# SMT_2inch_printer_060903.net
KiCad netlist of a schematic drawn in Altium Designer
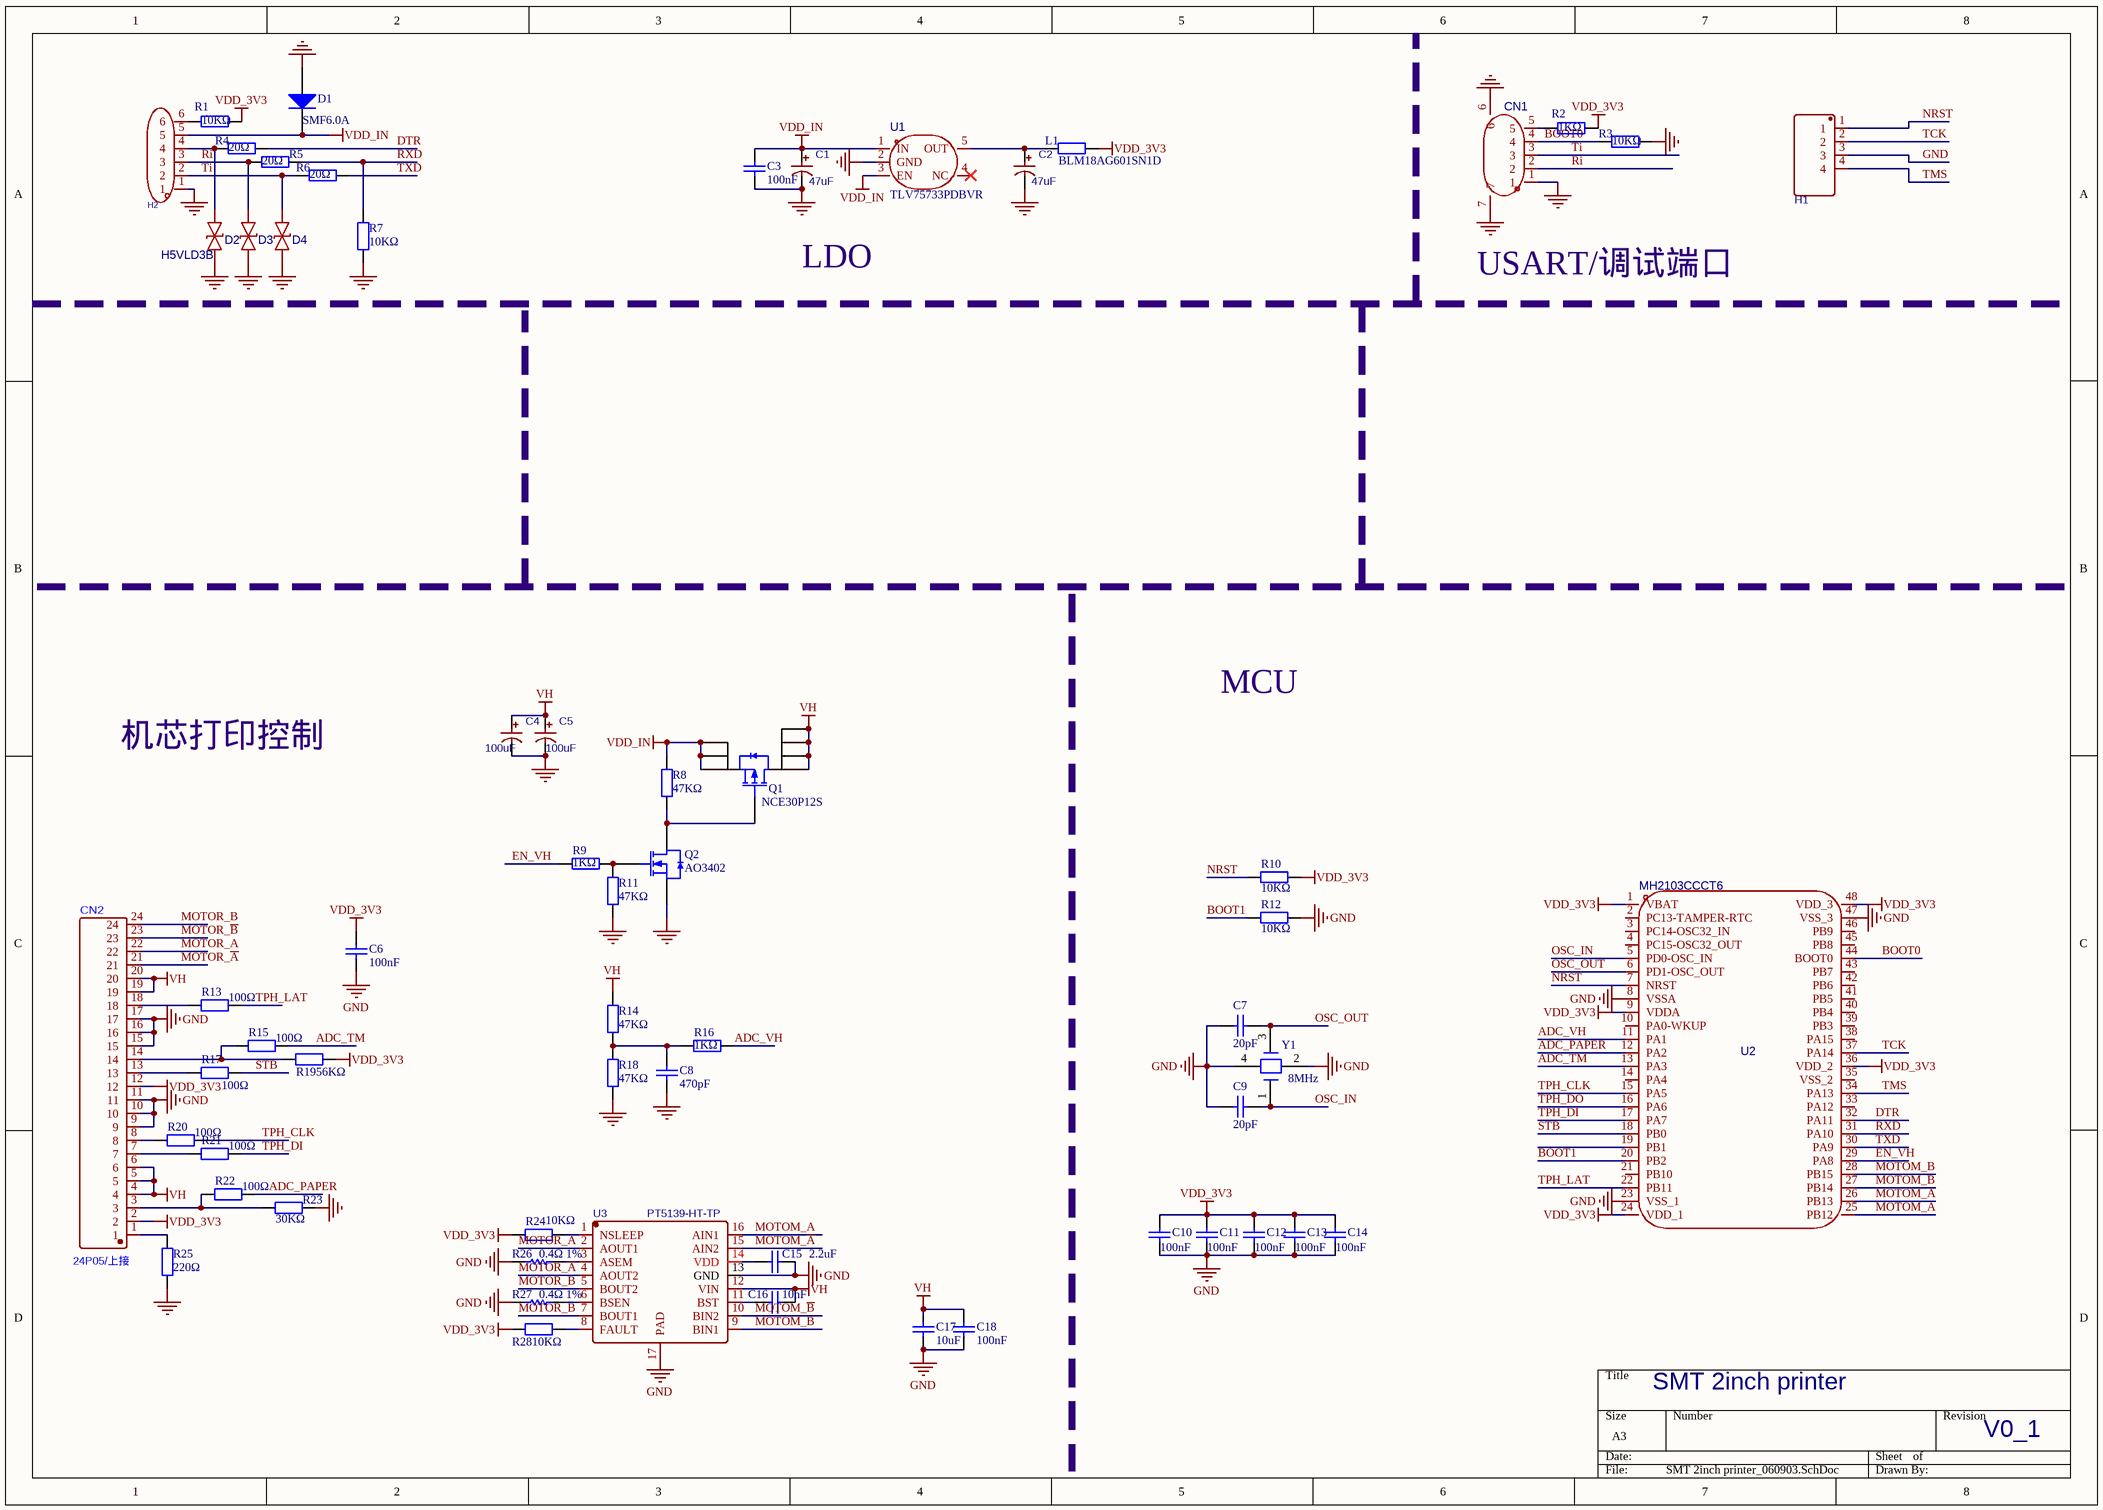
[diagram p0: SMT 2inch printer_060903.SchDoc]

(export (version "E")
  (design (tool "Eeschema 10.0.6"))
  (components
    (comp (ref "C1")
      (value "47uF")
      (footprint "CAP-SMD_BD6.3-L6.6-W6.6-FD")
      (fields
        (field (name "BOM_MANUFACTURER PART") "10uF 25V RHOS")
        (field (name "BOM_SUPPLIER PART") "C19576")
      )
      (libsource (lib "*") (part "10uF"))
    )
    (comp (ref "C2")
      (value "47uF")
      (footprint "CAP-SMD_BD6.3-L6.6-W6.6-FD")
      (fields
        (field (name "BOM_MANUFACTURER PART") "10uF 25V RHOS")
        (field (name "BOM_SUPPLIER PART") "C19576")
      )
      (libsource (lib "*") (part "10uF"))
    )
    (comp (ref "C3")
      (value "100nF")
      (footprint "0603_C")
      (description "贴片电容")
      (libsource (lib "*") (part "0603 100nF (104) 10% 50V"))
    )
    (comp (ref "C4")
      (value "100uF")
      (footprint "CAP-SMD_BD6.3-L6.6-W6.6-FD")
      (fields
        (field (name "BOM_MANUFACTURER PART") "10uF 25V RHOS")
        (field (name "BOM_SUPPLIER PART") "C19576")
      )
      (libsource (lib "*") (part "10uF"))
    )
    (comp (ref "C5")
      (value "100uF")
      (footprint "CAP-SMD_BD6.3-L6.6-W6.6-FD")
      (fields
        (field (name "BOM_MANUFACTURER PART") "10uF 25V RHOS")
        (field (name "BOM_SUPPLIER PART") "C19576")
      )
      (libsource (lib "*") (part "10uF"))
    )
    (comp (ref "C6")
      (value "100nF")
      (footprint "0603_C")
      (description "贴片电容")
      (libsource (lib "Miscellaneous Devices LC") (part "0603 100nF (104) 10% 50V"))
    )
    (comp (ref "C7")
      (value "20pF")
      (footprint "0603_C")
      (description "贴片电容")
      (libsource (lib "Miscellaneous Devices LC") (part "0603 10pF (100) 5% 50V"))
    )
    (comp (ref "C8")
      (value "470pF")
      (footprint "0603_C")
      (description "贴片电容")
      (libsource (lib "Miscellaneous Devices LC") (part "0603 100nF (104) 10% 50V"))
    )
    (comp (ref "C9")
      (value "20pF")
      (footprint "0603_C")
      (description "贴片电容")
      (libsource (lib "Miscellaneous Devices LC") (part "0603 10pF (100) 5% 50V"))
    )
    (comp (ref "C10")
      (value "100nF")
      (footprint "0603_C")
      (description "贴片电容")
      (libsource (lib "Miscellaneous Devices LC") (part "0603 100nF (104) 10% 50V"))
    )
    (comp (ref "C11")
      (value "100nF")
      (footprint "0603_C")
      (description "贴片电容")
      (libsource (lib "Miscellaneous Devices LC") (part "0603 100nF (104) 10% 50V"))
    )
    (comp (ref "C12")
      (value "100nF")
      (footprint "0603_C")
      (description "贴片电容")
      (libsource (lib "Miscellaneous Devices LC") (part "0603 100nF (104) 10% 50V"))
    )
    (comp (ref "C13")
      (value "100nF")
      (footprint "0603_C")
      (description "贴片电容")
      (libsource (lib "Miscellaneous Devices LC") (part "0603 100nF (104) 10% 50V"))
    )
    (comp (ref "C14")
      (value "100nF")
      (footprint "0603_C")
      (description "贴片电容")
      (libsource (lib "Miscellaneous Devices LC") (part "0603 100nF (104) 10% 50V"))
    )
    (comp (ref "C15")
      (value "2.2uF")
      (footprint "0603_C")
      (description "贴片电容")
      (libsource (lib "Miscellaneous Devices LC") (part "0805 2.2uF (225) 20% 50V"))
    )
    (comp (ref "C16")
      (value "10nF")
      (footprint "0603_C")
      (description "贴片电容")
      (libsource (lib "Miscellaneous Devices LC") (part "0603 10nF (103) 10% 50V"))
    )
    (comp (ref "C17")
      (value "10uF")
      (footprint "0603_C")
      (description "贴片电容")
      (libsource (lib "Miscellaneous Devices LC") (part "0805 10uF (106) 10% 25V"))
    )
    (comp (ref "C18")
      (value "100nF")
      (footprint "0603_C")
      (description "贴片电容")
      (libsource (lib "Miscellaneous Devices LC") (part "0603 100nF (104) 10% 50V"))
    )
    (comp (ref "CN1")
      (value "mx1.25mm-5p-wt")
      (footprint "CONN-SMD_5P-P1.25_MX1.25MM-5P-WT")
      (fields (field (name "MANUFACTURERPART") "MX1.25mm-5P-WT"))
      (libsource (lib "altium-import") (part "root_2_mx1.25mm-5p-wt_"))
    )
    (comp (ref "CN2")
      (value "24P05/上接")
      (footprint "FPC-SMD_24P-P0.50_F0500WR-S-24PNLNG1GB0R")
      (libsource (lib "altium-import") (part "root_2__"))
    )
    (comp (ref "D1")
      (value "SMF6.0A")
      (footprint "SOD-123FL_L2.7-W1.8-LS3.8-RD")
      (description "稳压二极管")
      (libsource (lib "*") (part "SOD-323 1N4148WS T4"))
    )
    (comp (ref "D2")
      (value "H5VLD3B")
      (footprint "SOD-323_L1.7-W1.3-LS2.5-BI")
      (libsource (lib "altium-import") (part "root_1_PESD5V0S1BA_C2827694_"))
    )
    (comp (ref "D3")
      (value "H5VLD3B")
      (footprint "SOD-323_L1.7-W1.3-LS2.5-BI")
      (libsource (lib "altium-import") (part "root_1_PESD5V0S1BA_C2827694_"))
    )
    (comp (ref "D4")
      (value "H5VLD3B")
      (footprint "SOD-323_L1.7-W1.3-LS2.5-BI")
      (libsource (lib "altium-import") (part "root_1_PESD5V0S1BA_C2827694_"))
    )
    (comp (ref "H1")
      (value "77311-462K05LF")
      (footprint "77311-462K05LF")
      (fields (field (name "BOM_SUPPLIER PART") "C180219") (field (name "CONTRIBUTOR") "LCSC"))
      (libsource (lib "*") (part "77311-462K05LF"))
    )
    (comp (ref "H2")
      (value "lail-pz2.54-6p-l")
      (footprint "HDR-TH_6P-P2.54-V-F")
      (fields (field (name "MANUFACTURERPART") "LAIL-PZ2.54-6P-L"))
      (libsource (lib "altium-import") (part "root_2_lail-pz2.54-6p-l_"))
    )
    (comp (ref "L1")
      (value "BLM18AG601SN1D")
      (footprint "0805_L")
      (description "贴片电阻")
      (libsource (lib "*") (part "0603 4.7KΩ (4701) 1%"))
    )
    (comp (ref "Q1")
      (value "NCE30P12S")
      (footprint "SOIC-8_150mil")
      (description "MOS(场效应管)")
      (libsource (lib "*") (part "AO4407A"))
    )
    (comp (ref "Q2")
      (value "AO3402")
      (footprint "SOT-23-3L")
      (description "MOS(场效应管)")
      (libsource (lib "*") (part "AO3402A N道沟 X0YV1T SOT-23"))
    )
    (comp (ref "R1")
      (value "10KΩ")
      (footprint "0603_R")
      (description "贴片电阻")
      (libsource (lib "*") (part "0603 4.7KΩ (4701) 1%"))
    )
    (comp (ref "R2")
      (value "1KΩ")
      (footprint "0603_R")
      (description "贴片电阻")
      (libsource (lib "*") (part "0603 4.7KΩ (4701) 1%"))
    )
    (comp (ref "R3")
      (value "10KΩ")
      (footprint "0603_R")
      (description "贴片电阻")
      (libsource (lib "*") (part "0603 4.7KΩ (4701) 1%"))
    )
    (comp (ref "R4")
      (value "20Ω")
      (footprint "0603_R")
      (description "贴片电阻")
      (libsource (lib "*") (part "0603 100Ω (1000) 1%"))
    )
    (comp (ref "R5")
      (value "20Ω")
      (footprint "0603_R")
      (description "贴片电阻")
      (libsource (lib "*") (part "0603 100Ω (1000) 1%"))
    )
    (comp (ref "R6")
      (value "20Ω")
      (footprint "0603_R")
      (description "贴片电阻")
      (libsource (lib "*") (part "0603 100Ω (1000) 1%"))
    )
    (comp (ref "R7")
      (value "10KΩ")
      (footprint "0603_R")
      (description "贴片电阻")
      (libsource (lib "") (part "0603 4.7KΩ (4701) 1%_2"))
    )
    (comp (ref "R8")
      (value "47KΩ")
      (footprint "0603_R")
      (description "贴片电阻")
      (libsource (lib "*") (part "0603 47KΩ (4702) 1%"))
    )
    (comp (ref "R9")
      (value "1KΩ")
      (footprint "0603_R")
      (description "贴片电阻")
      (libsource (lib "*") (part "0603 470Ω (4700) 1%"))
    )
    (comp (ref "R10")
      (value "10KΩ")
      (footprint "0603_R")
      (description "贴片电阻")
      (libsource (lib "Miscellaneous Devices LC") (part "0603 4.7KΩ (4701) 1%"))
    )
    (comp (ref "R11")
      (value "47KΩ")
      (footprint "0603_R")
      (description "贴片电阻")
      (libsource (lib "") (part "0603 4.7KΩ (4701) 1%_1"))
    )
    (comp (ref "R12")
      (value "10KΩ")
      (footprint "0603_R")
      (description "贴片电阻")
      (libsource (lib "Miscellaneous Devices LC") (part "0603 4.7KΩ (4701) 1%"))
    )
    (comp (ref "R13")
      (value "100Ω")
      (footprint "0603_R")
      (description "贴片电阻")
      (libsource (lib "Miscellaneous Devices LC") (part "0603 10KΩ (1002) 1%"))
    )
    (comp (ref "R14")
      (value "47KΩ")
      (footprint "0603_R")
      (description "贴片电阻")
      (libsource (lib "") (part "0603 4.7KΩ (4701) 1%_1"))
    )
    (comp (ref "R15")
      (value "100Ω")
      (footprint "0603_R")
      (description "贴片电阻")
      (libsource (lib "Miscellaneous Devices LC") (part "0603 10KΩ (1002) 1%"))
    )
    (comp (ref "R16")
      (value "1KΩ")
      (footprint "0603_R")
      (description "贴片电阻")
      (libsource (lib "*") (part "0603 470Ω (4700) 1%"))
    )
    (comp (ref "R17")
      (value "100Ω")
      (footprint "0603_R")
      (description "贴片电阻")
      (libsource (lib "Miscellaneous Devices LC") (part "0603 10KΩ (1002) 1%"))
    )
    (comp (ref "R18")
      (value "47KΩ")
      (footprint "0603_R")
      (description "贴片电阻")
      (libsource (lib "") (part "0603 4.7KΩ (4701) 1%_1"))
    )
    (comp (ref "R19")
      (value "56KΩ")
      (footprint "0603_R")
      (description "贴片电阻")
      (libsource (lib "Miscellaneous Devices LC") (part "0603 10KΩ (1002) 1%"))
    )
    (comp (ref "R20")
      (value "100Ω")
      (footprint "0603_R")
      (description "贴片电阻")
      (libsource (lib "Miscellaneous Devices LC") (part "0603 10KΩ (1002) 1%"))
    )
    (comp (ref "R21")
      (value "100Ω")
      (footprint "0603_R")
      (description "贴片电阻")
      (libsource (lib "Miscellaneous Devices LC") (part "0603 10KΩ (1002) 1%"))
    )
    (comp (ref "R22")
      (value "100Ω")
      (footprint "0603_R")
      (description "贴片电阻")
      (libsource (lib "Miscellaneous Devices LC") (part "0603 10KΩ (1002) 1%"))
    )
    (comp (ref "R23")
      (value "30KΩ")
      (footprint "0603_R")
      (description "贴片电阻")
      (libsource (lib "*") (part "0603 30KΩ (3002) 1%"))
    )
    (comp (ref "R24")
      (value "10KΩ")
      (footprint "0603_R")
      (description "贴片电阻")
      (libsource (lib "AD封装2018.9.19Miscellaneous Devices LC") (part "0603 10KΩ (1002) 1%"))
    )
    (comp (ref "R25")
      (value "220Ω")
      (footprint "0603_R")
      (description "贴片电阻")
      (libsource (lib "*") (part "0603 200Ω (2000) 1%"))
    )
    (comp (ref "R26")
      (value "0.4Ω 1%")
      (footprint "1206_R")
      (description "Resistor")
      (fields (field (name "PUBLISHER") "Altium Limited"))
      (libsource (lib "JM320") (part "Res"))
    )
    (comp (ref "R27")
      (value "0.4Ω 1%")
      (footprint "1206_R")
      (description "Resistor")
      (fields (field (name "PUBLISHER") "Altium Limited"))
      (libsource (lib "JM320") (part "Res"))
    )
    (comp (ref "R28")
      (value "10KΩ")
      (footprint "0603_R")
      (description "贴片电阻")
      (libsource (lib "AD封装2018.9.19Miscellaneous Devices LC") (part "0603 10KΩ (1002) 1%"))
    )
    (comp (ref "U1")
      (value "TLV75733PDBVR")
      (footprint "SOT-23-5")
      (libsource (lib "*") (part "TLV75733PDBVR"))
    )
    (comp (ref "U2")
      (value "MH2103CCCT6")
      (footprint "LQFP-48_L7.0-W7.0-P0.50-LS9.0-BL")
      (fields (field (name "MANUFACTURERPART") "STM32F103C8T6"))
      (libsource (lib "altium-import") (part "root_0_stm32f103c8t6_"))
    )
    (comp (ref "U3")
      (value "PT5139-HT-TP")
      (footprint "HTSSOP-16_L5.0-W4.4-P0.65-LS6.4-BL-EP")
      (fields (field (name "BOM_SUPPLIER PART") "C336601") (field (name "CONTRIBUTOR") "LCSC"))
      (libsource (lib "altium-import") (part "root_0_PT5139-HT-TP_"))
    )
    (comp (ref "Y1")
      (value "8MHz")
      (footprint "XT_3225_4")
      (description "Crystal Oscillator")
      (libsource (lib "JM320") (part "XTAL_4"))
    )
  )
  (nets
    (net (code "1") (name "/ADC_PAPER") (class "Default")
      (node (ref "R22") (pin "2") (pinfunction "2_2") (pintype "passive"))
      (node (ref "U2") (pin "12") (pinfunction "PA2_12") (pintype "passive"))
    )
    (net (code "2") (name "/ADC_TM") (class "Default")
      (node (ref "R15") (pin "2") (pinfunction "2_2") (pintype "passive"))
      (node (ref "U2") (pin "13") (pinfunction "PA3_13") (pintype "passive"))
    )
    (net (code "3") (name "/ADC_VH") (class "Default")
      (node (ref "R16") (pin "1") (pinfunction "1_1") (pintype "passive"))
      (node (ref "U2") (pin "11") (pinfunction "PA1_11") (pintype "passive"))
    )
    (net (code "4") (name "/BOOT0") (class "Default")
      (node (ref "CN1") (pin "4") (pinfunction "4_4") (pintype "passive"))
      (node (ref "R3") (pin "1") (pinfunction "1_1") (pintype "passive"))
      (node (ref "U2") (pin "44") (pinfunction "BOOT0_44") (pintype "passive"))
    )
    (net (code "5") (name "/BOOT1") (class "Default")
      (node (ref "R12") (pin "2") (pinfunction "2_2") (pintype "passive"))
      (node (ref "U2") (pin "20") (pinfunction "PB2_20") (pintype "passive"))
    )
    (net (code "6") (name "/DTR") (class "Default")
      (node (ref "R4") (pin "2") (pinfunction "2_2") (pintype "passive"))
      (node (ref "U2") (pin "32") (pinfunction "PA11_32") (pintype "passive"))
    )
    (net (code "7") (name "/EN_VH") (class "Default")
      (node (ref "R9") (pin "2") (pinfunction "2_2") (pintype "passive"))
      (node (ref "U2") (pin "29") (pinfunction "PA8_29") (pintype "passive"))
    )
    (net (code "8") (name "/MOTOM_A") (class "Default")
      (node (ref "U2") (pin "25") (pinfunction "PB12_25") (pintype "passive"))
      (node (ref "U3") (pin "16") (pinfunction "AIN1_16") (pintype "passive"))
    )
    (net (code "9") (name "/MOTOM_B") (class "Default")
      (node (ref "U2") (pin "28") (pinfunction "PB15_28") (pintype "passive"))
      (node (ref "U3") (pin "9") (pinfunction "BIN1_9") (pintype "passive"))
    )
    (net (code "10") (name "/MOTOM_~{A}") (class "Default")
      (node (ref "U2") (pin "26") (pinfunction "PB13_26") (pintype "passive"))
      (node (ref "U3") (pin "15") (pinfunction "AIN2_15") (pintype "passive"))
    )
    (net (code "11") (name "/MOTOM_~{B}") (class "Default")
      (node (ref "U2") (pin "27") (pinfunction "PB14_27") (pintype "passive"))
      (node (ref "U3") (pin "10") (pinfunction "BIN2_10") (pintype "passive"))
    )
    (net (code "12") (name "/MOTOR_A") (class "Default")
      (node (ref "CN2") (pin "22") (pinfunction "22_22") (pintype "passive"))
      (node (ref "U3") (pin "2") (pinfunction "AOUT1_2") (pintype "passive"))
    )
    (net (code "13") (name "/MOTOR_B") (class "Default")
      (node (ref "CN2") (pin "24") (pinfunction "24_24") (pintype "passive"))
      (node (ref "U3") (pin "7") (pinfunction "BOUT1_7") (pintype "passive"))
    )
    (net (code "14") (name "/MOTOR_~{A}") (class "Default")
      (node (ref "CN2") (pin "21") (pinfunction "21_21") (pintype "passive"))
      (node (ref "U3") (pin "4") (pinfunction "AOUT2_4") (pintype "passive"))
    )
    (net (code "15") (name "/MOTOR_~{B}") (class "Default")
      (node (ref "CN2") (pin "23") (pinfunction "23_23") (pintype "passive"))
      (node (ref "U3") (pin "5") (pinfunction "BOUT2_5") (pintype "passive"))
    )
    (net (code "16") (name "/NRST") (class "Default")
      (node (ref "H1") (pin "1") (pinfunction "1_1") (pintype "passive"))
      (node (ref "R10") (pin "2") (pinfunction "2_2") (pintype "passive"))
      (node (ref "U2") (pin "7") (pinfunction "NRST_7") (pintype "passive"))
    )
    (net (code "17") (name "/OSC_IN") (class "Default")
      (node (ref "C9") (pin "2") (pinfunction "2_2") (pintype "passive"))
      (node (ref "U2") (pin "5") (pinfunction "PD0-OSC_IN_5") (pintype "passive"))
      (node (ref "Y1") (pin "1") (pinfunction "OSC1_1") (pintype "passive"))
    )
    (net (code "18") (name "/OSC_OUT") (class "Default")
      (node (ref "C7") (pin "2") (pinfunction "2_2") (pintype "passive"))
      (node (ref "U2") (pin "6") (pinfunction "PD1-OSC_OUT_6") (pintype "passive"))
      (node (ref "Y1") (pin "3") (pinfunction "OSC2_3") (pintype "passive"))
    )
    (net (code "19") (name "/RXD") (class "Default")
      (node (ref "R5") (pin "2") (pinfunction "2_2") (pintype "passive"))
      (node (ref "R7") (pin "2") (pinfunction "2_2") (pintype "passive"))
      (node (ref "U2") (pin "31") (pinfunction "PA10_31") (pintype "passive"))
    )
    (net (code "20") (name "/Ri") (class "Default")
      (node (ref "CN1") (pin "2") (pinfunction "2_2") (pintype "passive"))
      (node (ref "D3") (pin "2") (pinfunction "2_2") (pintype "passive"))
      (node (ref "H2") (pin "3") (pinfunction "3_3") (pintype "passive"))
      (node (ref "R5") (pin "1") (pinfunction "1_1") (pintype "passive"))
    )
    (net (code "21") (name "/STB") (class "Default")
      (node (ref "R17") (pin "2") (pinfunction "2_2") (pintype "passive"))
      (node (ref "U2") (pin "18") (pinfunction "PB0_18") (pintype "passive"))
    )
    (net (code "22") (name "/TCK") (class "Default")
      (node (ref "H1") (pin "2") (pinfunction "2_2") (pintype "passive"))
      (node (ref "U2") (pin "37") (pinfunction "PA14_37") (pintype "passive"))
    )
    (net (code "23") (name "/TMS") (class "Default")
      (node (ref "H1") (pin "4") (pinfunction "4_4") (pintype "passive"))
      (node (ref "U2") (pin "34") (pinfunction "PA13_34") (pintype "passive"))
    )
    (net (code "24") (name "/TPH_CLK") (class "Default")
      (node (ref "R20") (pin "2") (pinfunction "2_2") (pintype "passive"))
      (node (ref "U2") (pin "15") (pinfunction "PA5_15") (pintype "passive"))
    )
    (net (code "25") (name "/TPH_DI") (class "Default")
      (node (ref "R21") (pin "2") (pinfunction "2_2") (pintype "passive"))
      (node (ref "U2") (pin "17") (pinfunction "PA7_17") (pintype "passive"))
    )
    (net (code "26") (name "/TPH_DO") (class "Default")
      (node (ref "U2") (pin "16") (pinfunction "PA6_16") (pintype "passive"))
    )
    (net (code "27") (name "/TPH_LAT") (class "Default")
      (node (ref "R13") (pin "2") (pinfunction "2_2") (pintype "passive"))
      (node (ref "U2") (pin "22") (pinfunction "PB11_22") (pintype "passive"))
    )
    (net (code "28") (name "/TXD") (class "Default")
      (node (ref "R6") (pin "2") (pinfunction "2_2") (pintype "passive"))
      (node (ref "U2") (pin "30") (pinfunction "PA9_30") (pintype "passive"))
    )
    (net (code "29") (name "/Ti") (class "Default")
      (node (ref "CN1") (pin "3") (pinfunction "3_3") (pintype "passive"))
      (node (ref "D4") (pin "2") (pinfunction "2_2") (pintype "passive"))
      (node (ref "H2") (pin "2") (pinfunction "2_2") (pintype "passive"))
      (node (ref "R6") (pin "1") (pinfunction "1_1") (pintype "passive"))
    )
    (net (code "30") (name "GND") (class "Default")
      (node (ref "C1") (pin "2") (pinfunction "2_2") (pintype "passive"))
      (node (ref "C10") (pin "1") (pinfunction "1_1") (pintype "passive"))
      (node (ref "C11") (pin "1") (pinfunction "1_1") (pintype "passive"))
      (node (ref "C12") (pin "1") (pinfunction "1_1") (pintype "passive"))
      (node (ref "C13") (pin "1") (pinfunction "1_1") (pintype "passive"))
      (node (ref "C14") (pin "1") (pinfunction "1_1") (pintype "passive"))
      (node (ref "C15") (pin "2") (pinfunction "2_2") (pintype "passive"))
      (node (ref "C17") (pin "1") (pinfunction "1_1") (pintype "passive"))
      (node (ref "C18") (pin "1") (pinfunction "1_1") (pintype "passive"))
      (node (ref "C2") (pin "2") (pinfunction "2_2") (pintype "passive"))
      (node (ref "C3") (pin "2") (pinfunction "2_2") (pintype "passive"))
      (node (ref "C4") (pin "2") (pinfunction "2_2") (pintype "passive"))
      (node (ref "C5") (pin "2") (pinfunction "2_2") (pintype "passive"))
      (node (ref "C6") (pin "1") (pinfunction "1_1") (pintype "passive"))
      (node (ref "C7") (pin "1") (pinfunction "1_1") (pintype "passive"))
      (node (ref "C8") (pin "1") (pinfunction "1_1") (pintype "passive"))
      (node (ref "C9") (pin "1") (pinfunction "1_1") (pintype "passive"))
      (node (ref "CN1") (pin "1") (pinfunction "1_1") (pintype "passive"))
      (node (ref "CN1") (pin "6") (pinfunction "6_6") (pintype "passive"))
      (node (ref "CN1") (pin "7") (pinfunction "7_7") (pintype "passive"))
      (node (ref "CN2") (pin "10") (pinfunction "10_10") (pintype "passive"))
      (node (ref "CN2") (pin "11") (pinfunction "11_11") (pintype "passive"))
      (node (ref "CN2") (pin "15") (pinfunction "15_15") (pintype "passive"))
      (node (ref "CN2") (pin "16") (pinfunction "16_16") (pintype "passive"))
      (node (ref "CN2") (pin "17") (pinfunction "17_17") (pintype "passive"))
      (node (ref "CN2") (pin "9") (pinfunction "9_9") (pintype "passive"))
      (node (ref "D1") (pin "1") (pinfunction "A_1") (pintype "passive"))
      (node (ref "D2") (pin "1") (pinfunction "1_1") (pintype "passive"))
      (node (ref "D3") (pin "1") (pinfunction "1_1") (pintype "passive"))
      (node (ref "D4") (pin "1") (pinfunction "1_1") (pintype "passive"))
      (node (ref "H1") (pin "3") (pinfunction "3_3") (pintype "passive"))
      (node (ref "H2") (pin "1") (pinfunction "1_1") (pintype "passive"))
      (node (ref "Q2") (pin "2") (pinfunction "S_2") (pintype "passive"))
      (node (ref "R11") (pin "2") (pinfunction "2_2") (pintype "passive"))
      (node (ref "R12") (pin "1") (pinfunction "1_1") (pintype "passive"))
      (node (ref "R18") (pin "2") (pinfunction "2_2") (pintype "passive"))
      (node (ref "R23") (pin "2") (pinfunction "2_2") (pintype "passive"))
      (node (ref "R25") (pin "1") (pinfunction "1_1") (pintype "passive"))
      (node (ref "R26") (pin "2") (pinfunction "2_2") (pintype "passive"))
      (node (ref "R27") (pin "2") (pinfunction "2_2") (pintype "passive"))
      (node (ref "R3") (pin "2") (pinfunction "2_2") (pintype "passive"))
      (node (ref "R7") (pin "1") (pinfunction "1_1") (pintype "passive"))
      (node (ref "U1") (pin "2") (pinfunction "GND_2") (pintype "passive"))
      (node (ref "U2") (pin "23") (pinfunction "VSS_1_23") (pintype "passive"))
      (node (ref "U2") (pin "47") (pinfunction "VSS_3_47") (pintype "passive"))
      (node (ref "U2") (pin "8") (pinfunction "VSSA_8") (pintype "passive"))
      (node (ref "U3") (pin "13") (pinfunction "GND_13") (pintype "passive"))
      (node (ref "U3") (pin "17") (pinfunction "PAD_17") (pintype "passive"))
      (node (ref "Y1") (pin "2") (pinfunction "5_2") (pintype "passive"))
      (node (ref "Y1") (pin "4") (pinfunction "4_4") (pintype "passive"))
    )
    (net (code "31") (name "Net-(C8-Pad2)") (class "Default")
      (node (ref "C8") (pin "2") (pinfunction "2_2") (pintype "passive"))
      (node (ref "R14") (pin "2") (pinfunction "2_2") (pintype "passive"))
      (node (ref "R16") (pin "2") (pinfunction "2_2") (pintype "passive"))
      (node (ref "R18") (pin "1") (pinfunction "1_1") (pintype "passive"))
    )
    (net (code "32") (name "Net-(CN1-Pad5)") (class "Default")
      (node (ref "CN1") (pin "5") (pinfunction "5_5") (pintype "passive"))
      (node (ref "R2") (pin "1") (pinfunction "1_1") (pintype "passive"))
    )
    (net (code "33") (name "Net-(CN2-Pad1)") (class "Default")
      (node (ref "CN2") (pin "1") (pinfunction "1_1") (pintype "passive"))
      (node (ref "R25") (pin "2") (pinfunction "2_2") (pintype "passive"))
    )
    (net (code "34") (name "Net-(CN2-Pad3)") (class "Default")
      (node (ref "CN2") (pin "3") (pinfunction "3_3") (pintype "passive"))
      (node (ref "R22") (pin "1") (pinfunction "1_1") (pintype "passive"))
      (node (ref "R23") (pin "1") (pinfunction "1_1") (pintype "passive"))
    )
    (net (code "35") (name "Net-(CN2-Pad7)") (class "Default")
      (node (ref "CN2") (pin "7") (pinfunction "7_7") (pintype "passive"))
      (node (ref "R21") (pin "1") (pinfunction "1_1") (pintype "passive"))
    )
    (net (code "36") (name "Net-(CN2-Pad8)") (class "Default")
      (node (ref "CN2") (pin "8") (pinfunction "8_8") (pintype "passive"))
      (node (ref "R20") (pin "1") (pinfunction "1_1") (pintype "passive"))
    )
    (net (code "37") (name "Net-(CN2-Pad13)") (class "Default")
      (node (ref "CN2") (pin "13") (pinfunction "13_13") (pintype "passive"))
      (node (ref "R17") (pin "1") (pinfunction "1_1") (pintype "passive"))
    )
    (net (code "38") (name "Net-(CN2-Pad14)") (class "Default")
      (node (ref "CN2") (pin "14") (pinfunction "14_14") (pintype "passive"))
      (node (ref "R15") (pin "1") (pinfunction "1_1") (pintype "passive"))
      (node (ref "R19") (pin "1") (pinfunction "1_1") (pintype "passive"))
    )
    (net (code "39") (name "Net-(CN2-Pad18)") (class "Default")
      (node (ref "CN2") (pin "18") (pinfunction "18_18") (pintype "passive"))
      (node (ref "R13") (pin "1") (pinfunction "1_1") (pintype "passive"))
    )
    (net (code "40") (name "Net-(D2-Pad2)") (class "Default")
      (node (ref "D2") (pin "2") (pinfunction "2_2") (pintype "passive"))
      (node (ref "H2") (pin "4") (pinfunction "4_4") (pintype "passive"))
      (node (ref "R4") (pin "1") (pinfunction "1_1") (pintype "passive"))
    )
    (net (code "41") (name "Net-(H2-Pad6)") (class "Default")
      (node (ref "H2") (pin "6") (pinfunction "6_6") (pintype "passive"))
      (node (ref "R1") (pin "1") (pinfunction "1_1") (pintype "passive"))
    )
    (net (code "42") (name "Net-(Q1-G)") (class "Default")
      (node (ref "Q1") (pin "4") (pinfunction "G_4") (pintype "passive"))
      (node (ref "Q2") (pin "3") (pinfunction "D_3") (pintype "passive"))
      (node (ref "R8") (pin "1") (pinfunction "1_1") (pintype "passive"))
    )
    (net (code "43") (name "Net-(Q2-G)") (class "Default")
      (node (ref "Q2") (pin "1") (pinfunction "G_1") (pintype "passive"))
      (node (ref "R11") (pin "1") (pinfunction "1_1") (pintype "passive"))
      (node (ref "R9") (pin "1") (pinfunction "1_1") (pintype "passive"))
    )
    (net (code "44") (name "Net-(U1-OUT)") (class "Default")
      (node (ref "C2") (pin "1") (pinfunction "1_1") (pintype "passive"))
      (node (ref "L1") (pin "1") (pinfunction "1_1") (pintype "passive"))
      (node (ref "U1") (pin "5") (pinfunction "OUT_5") (pintype "passive"))
    )
    (net (code "45") (name "Net-(U3-ASEM)") (class "Default")
      (node (ref "R26") (pin "1") (pinfunction "1_1") (pintype "passive"))
      (node (ref "U3") (pin "3") (pinfunction "ASEM_3") (pintype "passive"))
    )
    (net (code "46") (name "Net-(U3-BSEN)") (class "Default")
      (node (ref "R27") (pin "1") (pinfunction "1_1") (pintype "passive"))
      (node (ref "U3") (pin "6") (pinfunction "BSEN_6") (pintype "passive"))
    )
    (net (code "47") (name "Net-(U3-BST)") (class "Default")
      (node (ref "C16") (pin "1") (pinfunction "1_1") (pintype "passive"))
      (node (ref "U3") (pin "11") (pinfunction "BST_11") (pintype "passive"))
    )
    (net (code "48") (name "Net-(U3-FAULT)") (class "Default")
      (node (ref "R28") (pin "1") (pinfunction "1_1") (pintype "passive"))
      (node (ref "U3") (pin "8") (pinfunction "FAULT_8") (pintype "passive"))
    )
    (net (code "49") (name "Net-(U3-NSLEEP)") (class "Default")
      (node (ref "R24") (pin "1") (pinfunction "1_1") (pintype "passive"))
      (node (ref "U3") (pin "1") (pinfunction "NSLEEP_1") (pintype "passive"))
    )
    (net (code "50") (name "Net-(U3-VDD)") (class "Default")
      (node (ref "C15") (pin "1") (pinfunction "1_1") (pintype "passive"))
      (node (ref "U3") (pin "14") (pinfunction "VDD_14") (pintype "passive"))
    )
    (net (code "51") (name "VDD_3V3") (class "Default")
      (node (ref "C10") (pin "2") (pinfunction "2_2") (pintype "passive"))
      (node (ref "C11") (pin "2") (pinfunction "2_2") (pintype "passive"))
      (node (ref "C12") (pin "2") (pinfunction "2_2") (pintype "passive"))
      (node (ref "C13") (pin "2") (pinfunction "2_2") (pintype "passive"))
      (node (ref "C14") (pin "2") (pinfunction "2_2") (pintype "passive"))
      (node (ref "C6") (pin "2") (pinfunction "2_2") (pintype "passive"))
      (node (ref "CN2") (pin "12") (pinfunction "12_12") (pintype "passive"))
      (node (ref "CN2") (pin "2") (pinfunction "2_2") (pintype "passive"))
      (node (ref "L1") (pin "2") (pinfunction "2_2") (pintype "passive"))
      (node (ref "R1") (pin "2") (pinfunction "2_2") (pintype "passive"))
      (node (ref "R10") (pin "1") (pinfunction "1_1") (pintype "passive"))
      (node (ref "R19") (pin "2") (pinfunction "2_2") (pintype "passive"))
      (node (ref "R2") (pin "2") (pinfunction "2_2") (pintype "passive"))
      (node (ref "R24") (pin "2") (pinfunction "2_2") (pintype "passive"))
      (node (ref "R28") (pin "2") (pinfunction "2_2") (pintype "passive"))
      (node (ref "U2") (pin "1") (pinfunction "VBAT_1") (pintype "passive"))
      (node (ref "U2") (pin "24") (pinfunction "VDD_1_24") (pintype "passive"))
      (node (ref "U2") (pin "36") (pinfunction "VDD_2_36") (pintype "passive"))
      (node (ref "U2") (pin "48") (pinfunction "VDD_3_48") (pintype "passive"))
      (node (ref "U2") (pin "9") (pinfunction "VDDA_9") (pintype "passive"))
    )
    (net (code "52") (name "VDD_IN") (class "Default")
      (node (ref "C1") (pin "1") (pinfunction "1_1") (pintype "passive"))
      (node (ref "C3") (pin "1") (pinfunction "1_1") (pintype "passive"))
      (node (ref "D1") (pin "2") (pinfunction "K_2") (pintype "passive"))
      (node (ref "H2") (pin "5") (pinfunction "5_5") (pintype "passive"))
      (node (ref "Q1") (pin "1") (pinfunction "S_1") (pintype "passive"))
      (node (ref "Q1") (pin "2") (pinfunction "S_2") (pintype "passive"))
      (node (ref "Q1") (pin "3") (pinfunction "S_3") (pintype "passive"))
      (node (ref "R8") (pin "2") (pinfunction "2_2") (pintype "passive"))
      (node (ref "U1") (pin "1") (pinfunction "IN_1") (pintype "passive"))
      (node (ref "U1") (pin "3") (pinfunction "EN_3") (pintype "passive"))
    )
    (net (code "53") (name "VH") (class "Default")
      (node (ref "C16") (pin "2") (pinfunction "2_2") (pintype "passive"))
      (node (ref "C17") (pin "2") (pinfunction "2_2") (pintype "passive"))
      (node (ref "C18") (pin "2") (pinfunction "2_2") (pintype "passive"))
      (node (ref "C4") (pin "1") (pinfunction "1_1") (pintype "passive"))
      (node (ref "C5") (pin "1") (pinfunction "1_1") (pintype "passive"))
      (node (ref "CN2") (pin "19") (pinfunction "19_19") (pintype "passive"))
      (node (ref "CN2") (pin "20") (pinfunction "20_20") (pintype "passive"))
      (node (ref "CN2") (pin "4") (pinfunction "4_4") (pintype "passive"))
      (node (ref "CN2") (pin "5") (pinfunction "5_5") (pintype "passive"))
      (node (ref "CN2") (pin "6") (pinfunction "6_6") (pintype "passive"))
      (node (ref "Q1") (pin "5") (pinfunction "D_5") (pintype "passive"))
      (node (ref "Q1") (pin "6") (pinfunction "D_6") (pintype "passive"))
      (node (ref "Q1") (pin "7") (pinfunction "D_7") (pintype "passive"))
      (node (ref "Q1") (pin "8") (pinfunction "D_8") (pintype "passive"))
      (node (ref "R14") (pin "1") (pinfunction "1_1") (pintype "passive"))
      (node (ref "U3") (pin "12") (pinfunction "VIN_12") (pintype "passive"))
    )
    (net (code "54") (name "unconnected-(U1-NC-Pad4)") (class "Default")
      (node (ref "U1") (pin "4") (pinfunction "NC_4") (pintype "passive+no_connect"))
    )
    (net (code "55") (name "unconnected-(U2-PA0-WKUP-Pad10)") (class "Default")
      (node (ref "U2") (pin "10") (pinfunction "PA0-WKUP_10") (pintype "passive"))
    )
    (net (code "56") (name "unconnected-(U2-PA4-Pad14)") (class "Default")
      (node (ref "U2") (pin "14") (pinfunction "PA4_14") (pintype "passive"))
    )
    (net (code "57") (name "unconnected-(U2-PA12-Pad33)") (class "Default")
      (node (ref "U2") (pin "33") (pinfunction "PA12_33") (pintype "passive"))
    )
    (net (code "58") (name "unconnected-(U2-PA15-Pad38)") (class "Default")
      (node (ref "U2") (pin "38") (pinfunction "PA15_38") (pintype "passive"))
    )
    (net (code "59") (name "unconnected-(U2-PB1-Pad19)") (class "Default")
      (node (ref "U2") (pin "19") (pinfunction "PB1_19") (pintype "passive"))
    )
    (net (code "60") (name "unconnected-(U2-PB3-Pad39)") (class "Default")
      (node (ref "U2") (pin "39") (pinfunction "PB3_39") (pintype "passive"))
    )
    (net (code "61") (name "unconnected-(U2-PB4-Pad40)") (class "Default")
      (node (ref "U2") (pin "40") (pinfunction "PB4_40") (pintype "passive"))
    )
    (net (code "62") (name "unconnected-(U2-PB5-Pad41)") (class "Default")
      (node (ref "U2") (pin "41") (pinfunction "PB5_41") (pintype "passive"))
    )
    (net (code "63") (name "unconnected-(U2-PB6-Pad42)") (class "Default")
      (node (ref "U2") (pin "42") (pinfunction "PB6_42") (pintype "passive"))
    )
    (net (code "64") (name "unconnected-(U2-PB7-Pad43)") (class "Default")
      (node (ref "U2") (pin "43") (pinfunction "PB7_43") (pintype "passive"))
    )
    (net (code "65") (name "unconnected-(U2-PB8-Pad45)") (class "Default")
      (node (ref "U2") (pin "45") (pinfunction "PB8_45") (pintype "passive"))
    )
    (net (code "66") (name "unconnected-(U2-PB9-Pad46)") (class "Default")
      (node (ref "U2") (pin "46") (pinfunction "PB9_46") (pintype "passive"))
    )
    (net (code "67") (name "unconnected-(U2-PB10-Pad21)") (class "Default")
      (node (ref "U2") (pin "21") (pinfunction "PB10_21") (pintype "passive"))
    )
    (net (code "68") (name "unconnected-(U2-PC13-TAMPER-RTC-Pad2)") (class "Default")
      (node (ref "U2") (pin "2") (pinfunction "PC13-TAMPER-RTC_2") (pintype "passive"))
    )
    (net (code "69") (name "unconnected-(U2-PC14-OSC32_IN-Pad3)") (class "Default")
      (node (ref "U2") (pin "3") (pinfunction "PC14-OSC32_IN_3") (pintype "passive"))
    )
    (net (code "70") (name "unconnected-(U2-PC15-OSC32_OUT-Pad4)") (class "Default")
      (node (ref "U2") (pin "4") (pinfunction "PC15-OSC32_OUT_4") (pintype "passive"))
    )
    (net (code "71") (name "unconnected-(U2-VSS_2-Pad35)") (class "Default")
      (node (ref "U2") (pin "35") (pinfunction "VSS_2_35") (pintype "passive"))
    )
  )
)
